# FM_Simple_Regen.net
KiCad netlist of a schematic drawn in EAGLE
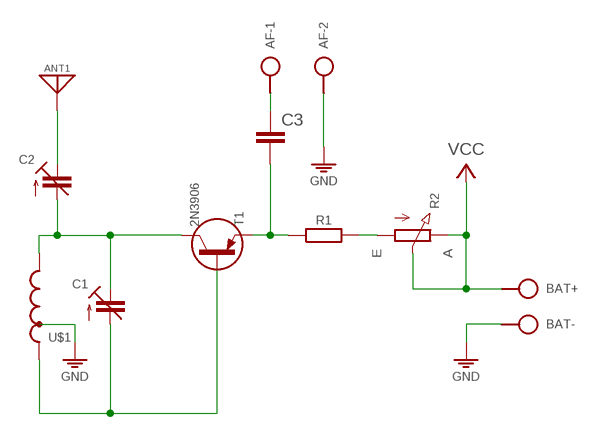
[diagram p0: schematic, sheet 1]

(export (version "E")
  (design (tool "Eeschema 10.0.6"))
  (components
    (comp (ref "AF")
      (value "SPAD-2")
      (footprint "eagle-import:SPAD-2")
      (libsource (lib "eagle-import") (part "SPAD-2"))
    )
    (comp (ref "ANT1")
      (value "ANT")
      (footprint "eagle-import:SPAD")
      (libsource (lib "eagle-import") (part "ANT"))
    )
    (comp (ref "BAT+")
      (value "SPAD")
      (footprint "eagle-import:SPAD")
      (libsource (lib "eagle-import") (part "SPAD"))
    )
    (comp (ref "BAT-")
      (value "SPAD")
      (footprint "eagle-import:SPAD")
      (libsource (lib "eagle-import") (part "SPAD"))
    )
    (comp (ref "C1")
      (value "C-TR-PH201272222-808-2PINB")
      (footprint "eagle-import:TRIM-2222-808")
      (libsource (lib "eagle-import") (part "C-TR-PH201272222-808-2PINB"))
    )
    (comp (ref "C2")
      (value "C-TR-PH201272222-808-2PIN")
      (footprint "eagle-import:TRIM-2222-808")
      (libsource (lib "eagle-import") (part "C-TR-PH201272222-808-2PIN"))
    )
    (comp (ref "C3")
      (value "C050-024X044")
      (footprint "eagle-import:C050-024X044")
      (libsource (lib "eagle-import") (part "C050-024X044"))
    )
    (comp (ref "R1")
      (value "R-H0204/10")
      (footprint "eagle-import:0204_10")
      (libsource (lib "eagle-import") (part "R-H0204/10"))
    )
    (comp (ref "R2")
      (value "POT")
      (footprint "eagle-import:POT")
      (libsource (lib "eagle-import") (part "POT"))
    )
    (comp (ref "T1")
      (value "2N3906")
      (footprint "eagle-import:TO92")
      (libsource (lib "eagle-import") (part "2N3906"))
    )
    (comp (ref "U$1")
      (value "L-TAP104/7")
      (footprint "eagle-import:L-04_7-TAP1")
      (libsource (lib "eagle-import") (part "L-TAP104/7"))
    )
  )
  (nets
    (net (code "1") (name "GND") (class "Default")
      (node (ref "AF") (pin "2") (pinfunction "P$1_2") (pintype "passive"))
      (node (ref "BAT-") (pin "1") (pinfunction "P$1_1") (pintype "passive"))
      (node (ref "U$1") (pin "T") (pinfunction "T_T") (pintype "passive"))
    )
    (net (code "2") (name "Net-(AFA-P$1)") (class "Default")
      (node (ref "AF") (pin "1") (pinfunction "P$1_1") (pintype "passive"))
      (node (ref "C3") (pin "1") (pinfunction "1_1") (pintype "passive"))
    )
    (net (code "3") (name "Net-(C1-A)") (class "Default")
      (node (ref "C1") (pin "2") (pinfunction "A_2") (pintype "passive"))
      (node (ref "T1") (pin "2") (pinfunction "B_2") (pintype "passive"))
      (node (ref "U$1") (pin "1") (pinfunction "1_1") (pintype "passive"))
    )
    (net (code "4") (name "Net-(C1-E)") (class "Default")
      (node (ref "C1") (pin "3") (pinfunction "E_3") (pintype "passive"))
      (node (ref "C2") (pin "2") (pinfunction "A_2") (pintype "passive"))
      (node (ref "T1") (pin "3") (pinfunction "C_3") (pintype "passive"))
      (node (ref "U$1") (pin "2") (pinfunction "2_2") (pintype "passive"))
    )
    (net (code "5") (name "Net-(C2-E)") (class "Default")
      (node (ref "ANT1") (pin "1") (pinfunction "1_1") (pintype "output"))
      (node (ref "C2") (pin "1") (pinfunction "E_1") (pintype "passive"))
    )
    (net (code "6") (name "Net-(R1-Pad2)") (class "Default")
      (node (ref "R1") (pin "2") (pinfunction "2_2") (pintype "passive"))
      (node (ref "R2") (pin "A") (pinfunction "A_A") (pintype "passive"))
    )
    (net (code "7") (name "Net-(T1-E)") (class "Default")
      (node (ref "C3") (pin "2") (pinfunction "2_2") (pintype "passive"))
      (node (ref "R1") (pin "1") (pinfunction "1_1") (pintype "passive"))
      (node (ref "T1") (pin "1") (pinfunction "E_1") (pintype "passive"))
    )
    (net (code "8") (name "VCC") (class "Default")
      (node (ref "BAT+") (pin "1") (pinfunction "P$1_1") (pintype "passive"))
      (node (ref "R2") (pin "E") (pinfunction "E_E") (pintype "passive"))
      (node (ref "R2") (pin "S") (pinfunction "S_S") (pintype "passive"))
    )
  )
)
